# MEB-Quectel-BG96-v1_2_0.net
KiCad netlist of a schematic drawn in EAGLE
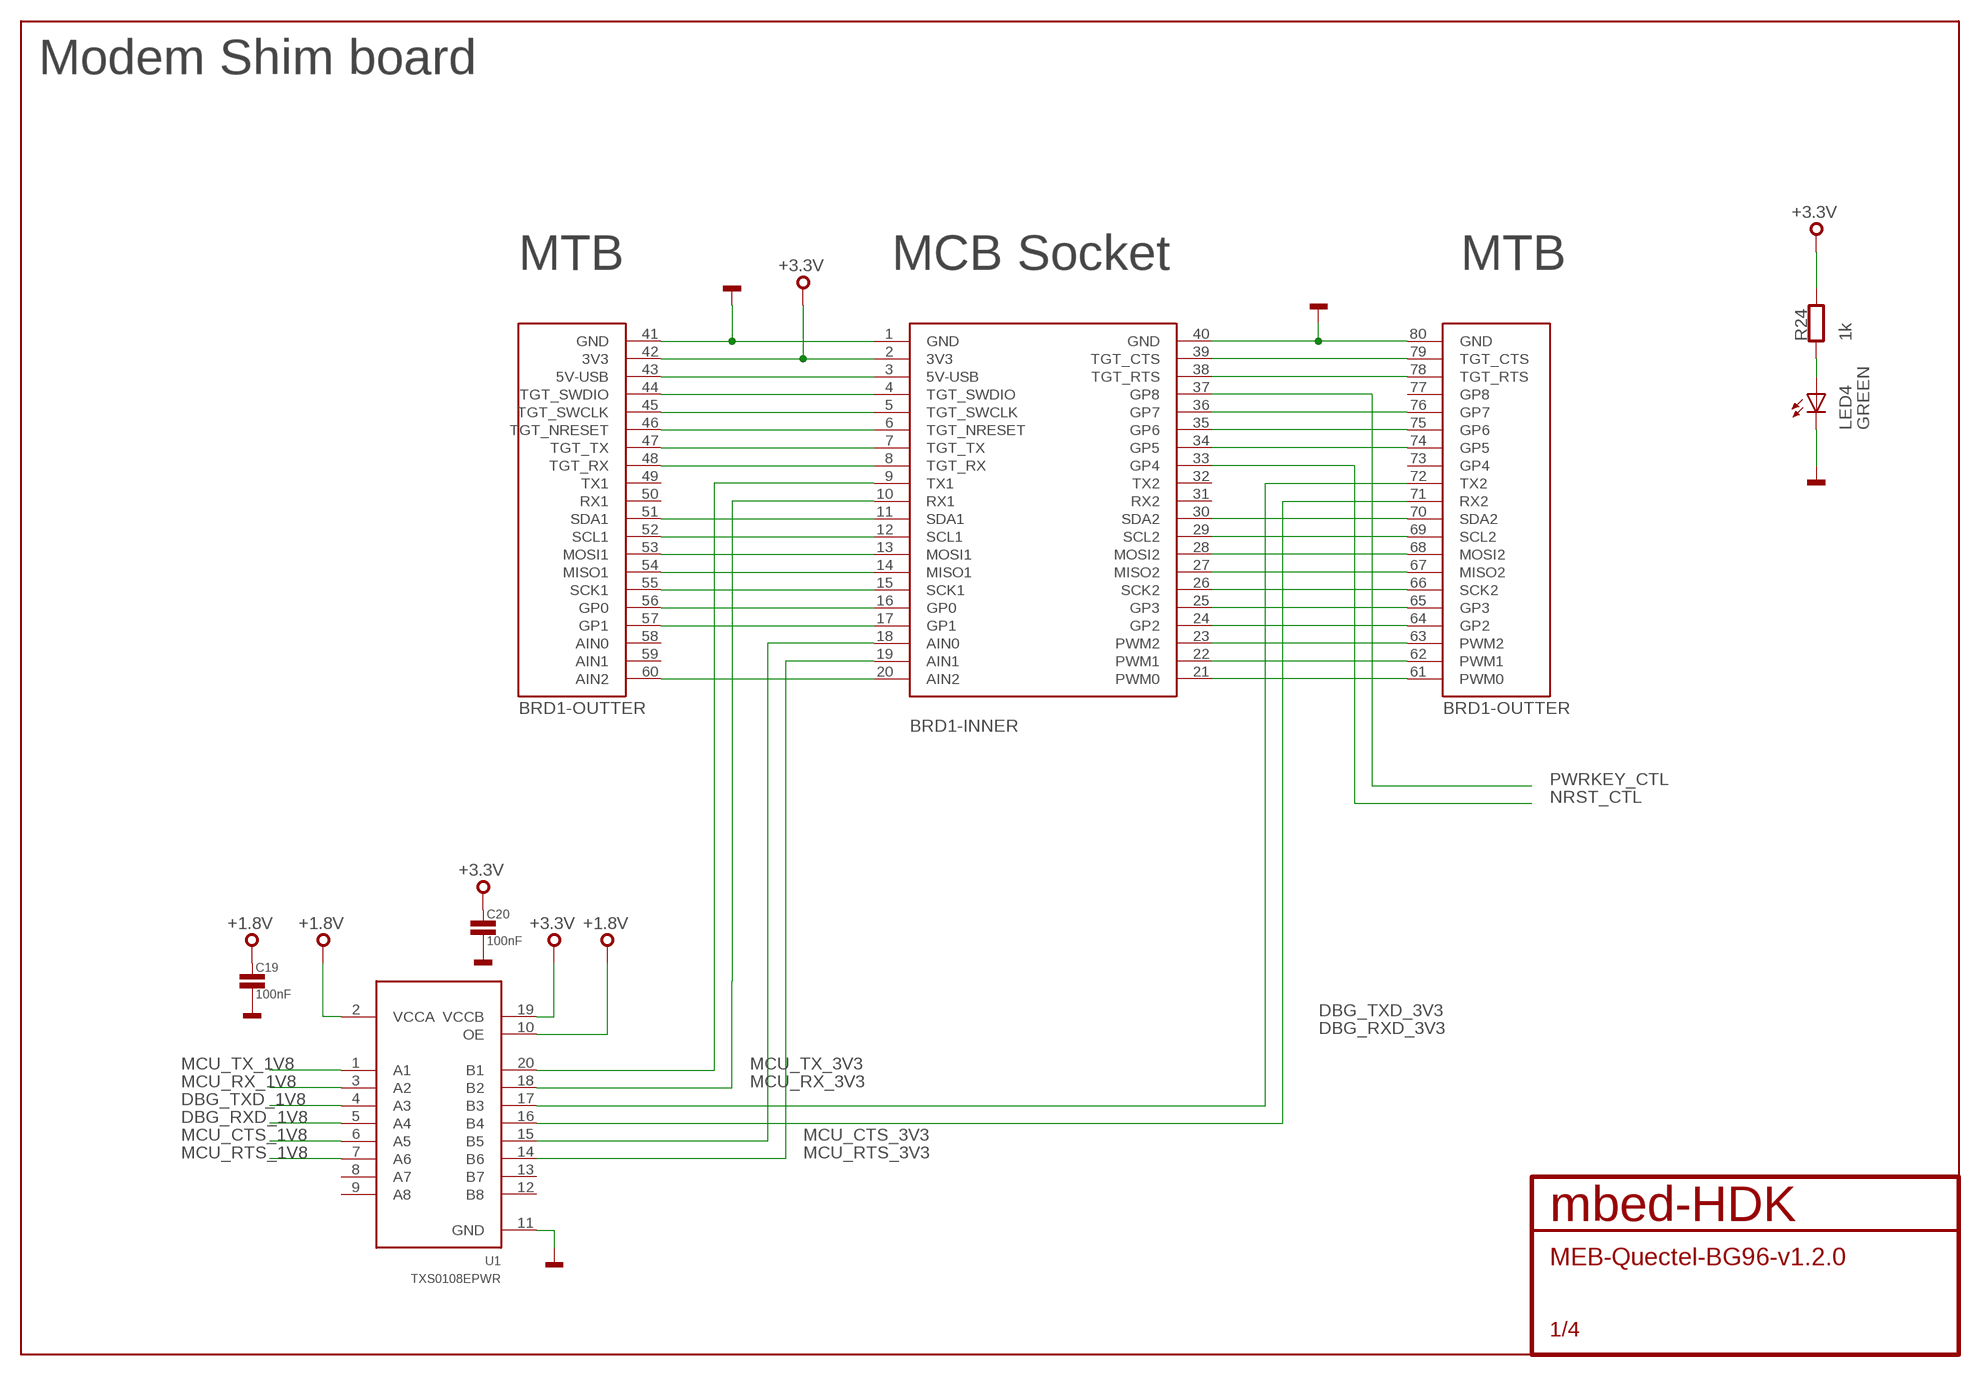
[diagram p0: schematic, sheet 1]
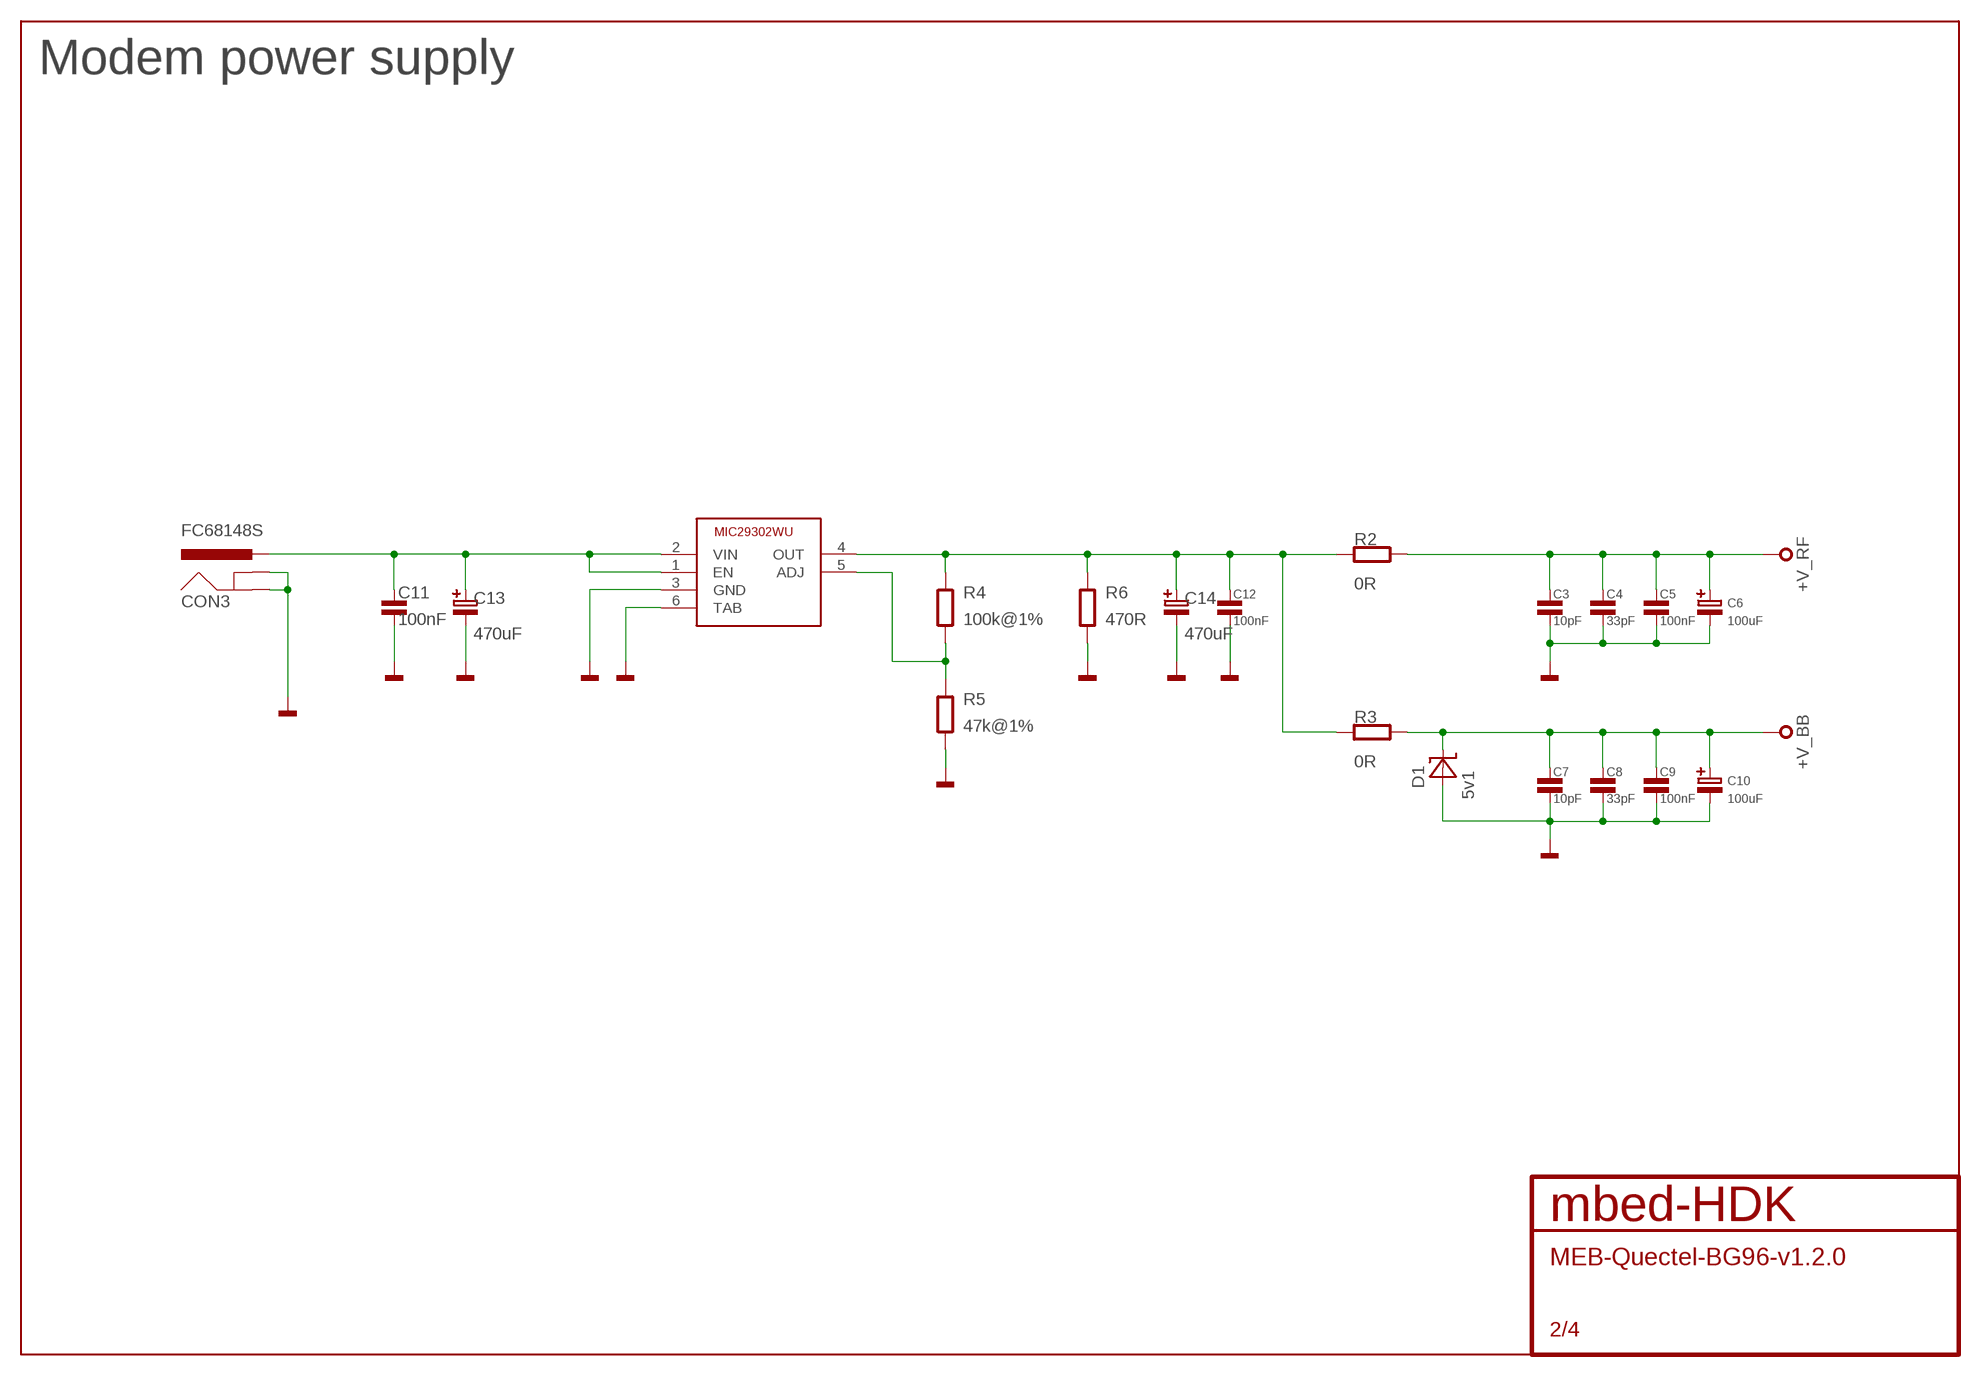
[diagram p1: schematic, sheet 2]
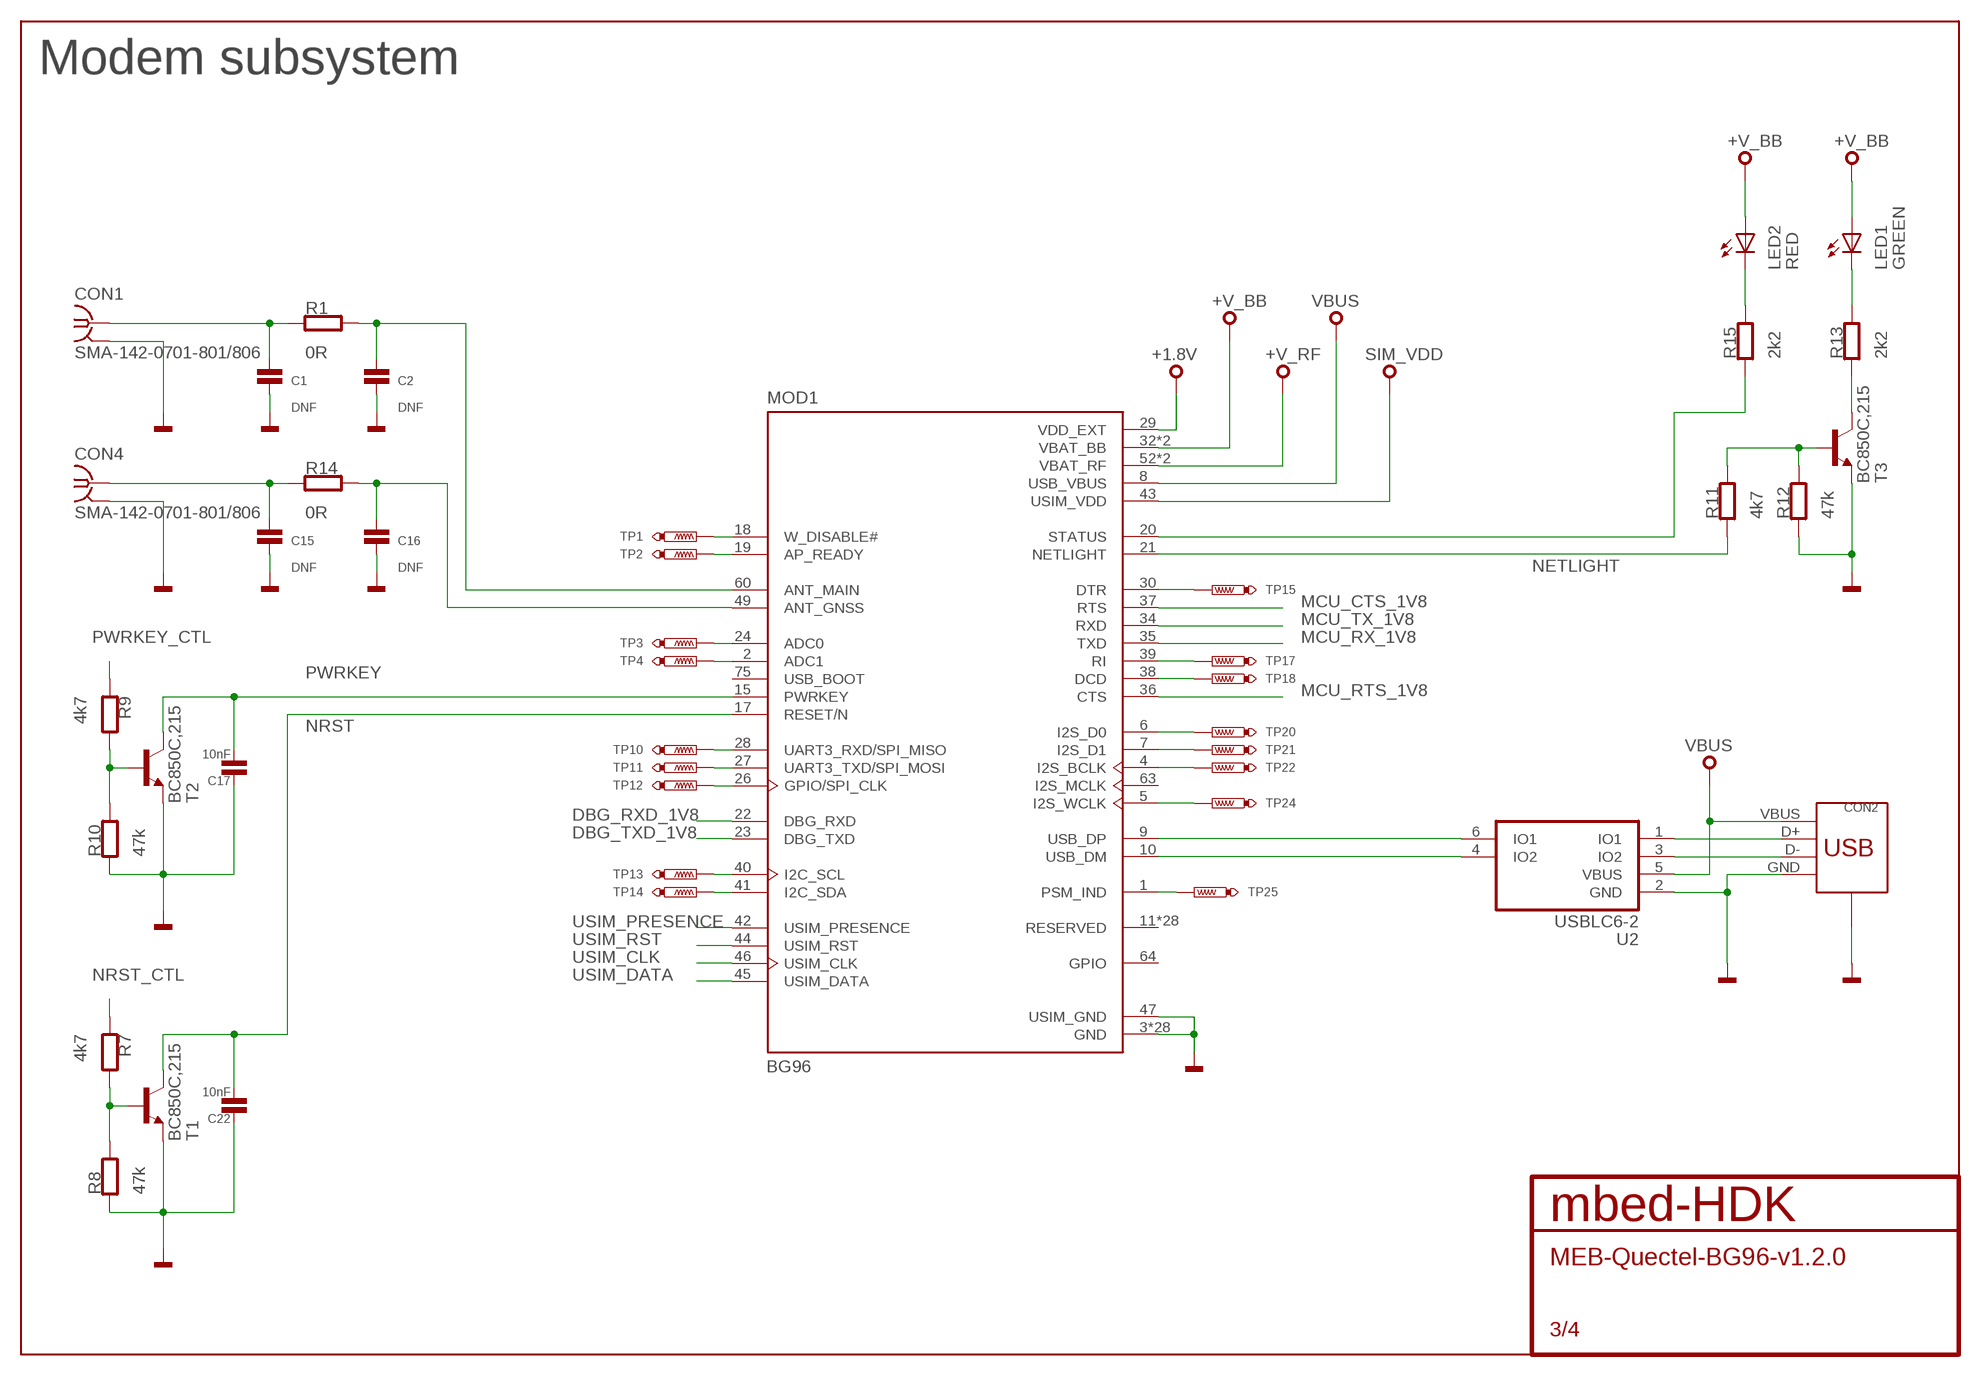
[diagram p2: schematic, sheet 3]
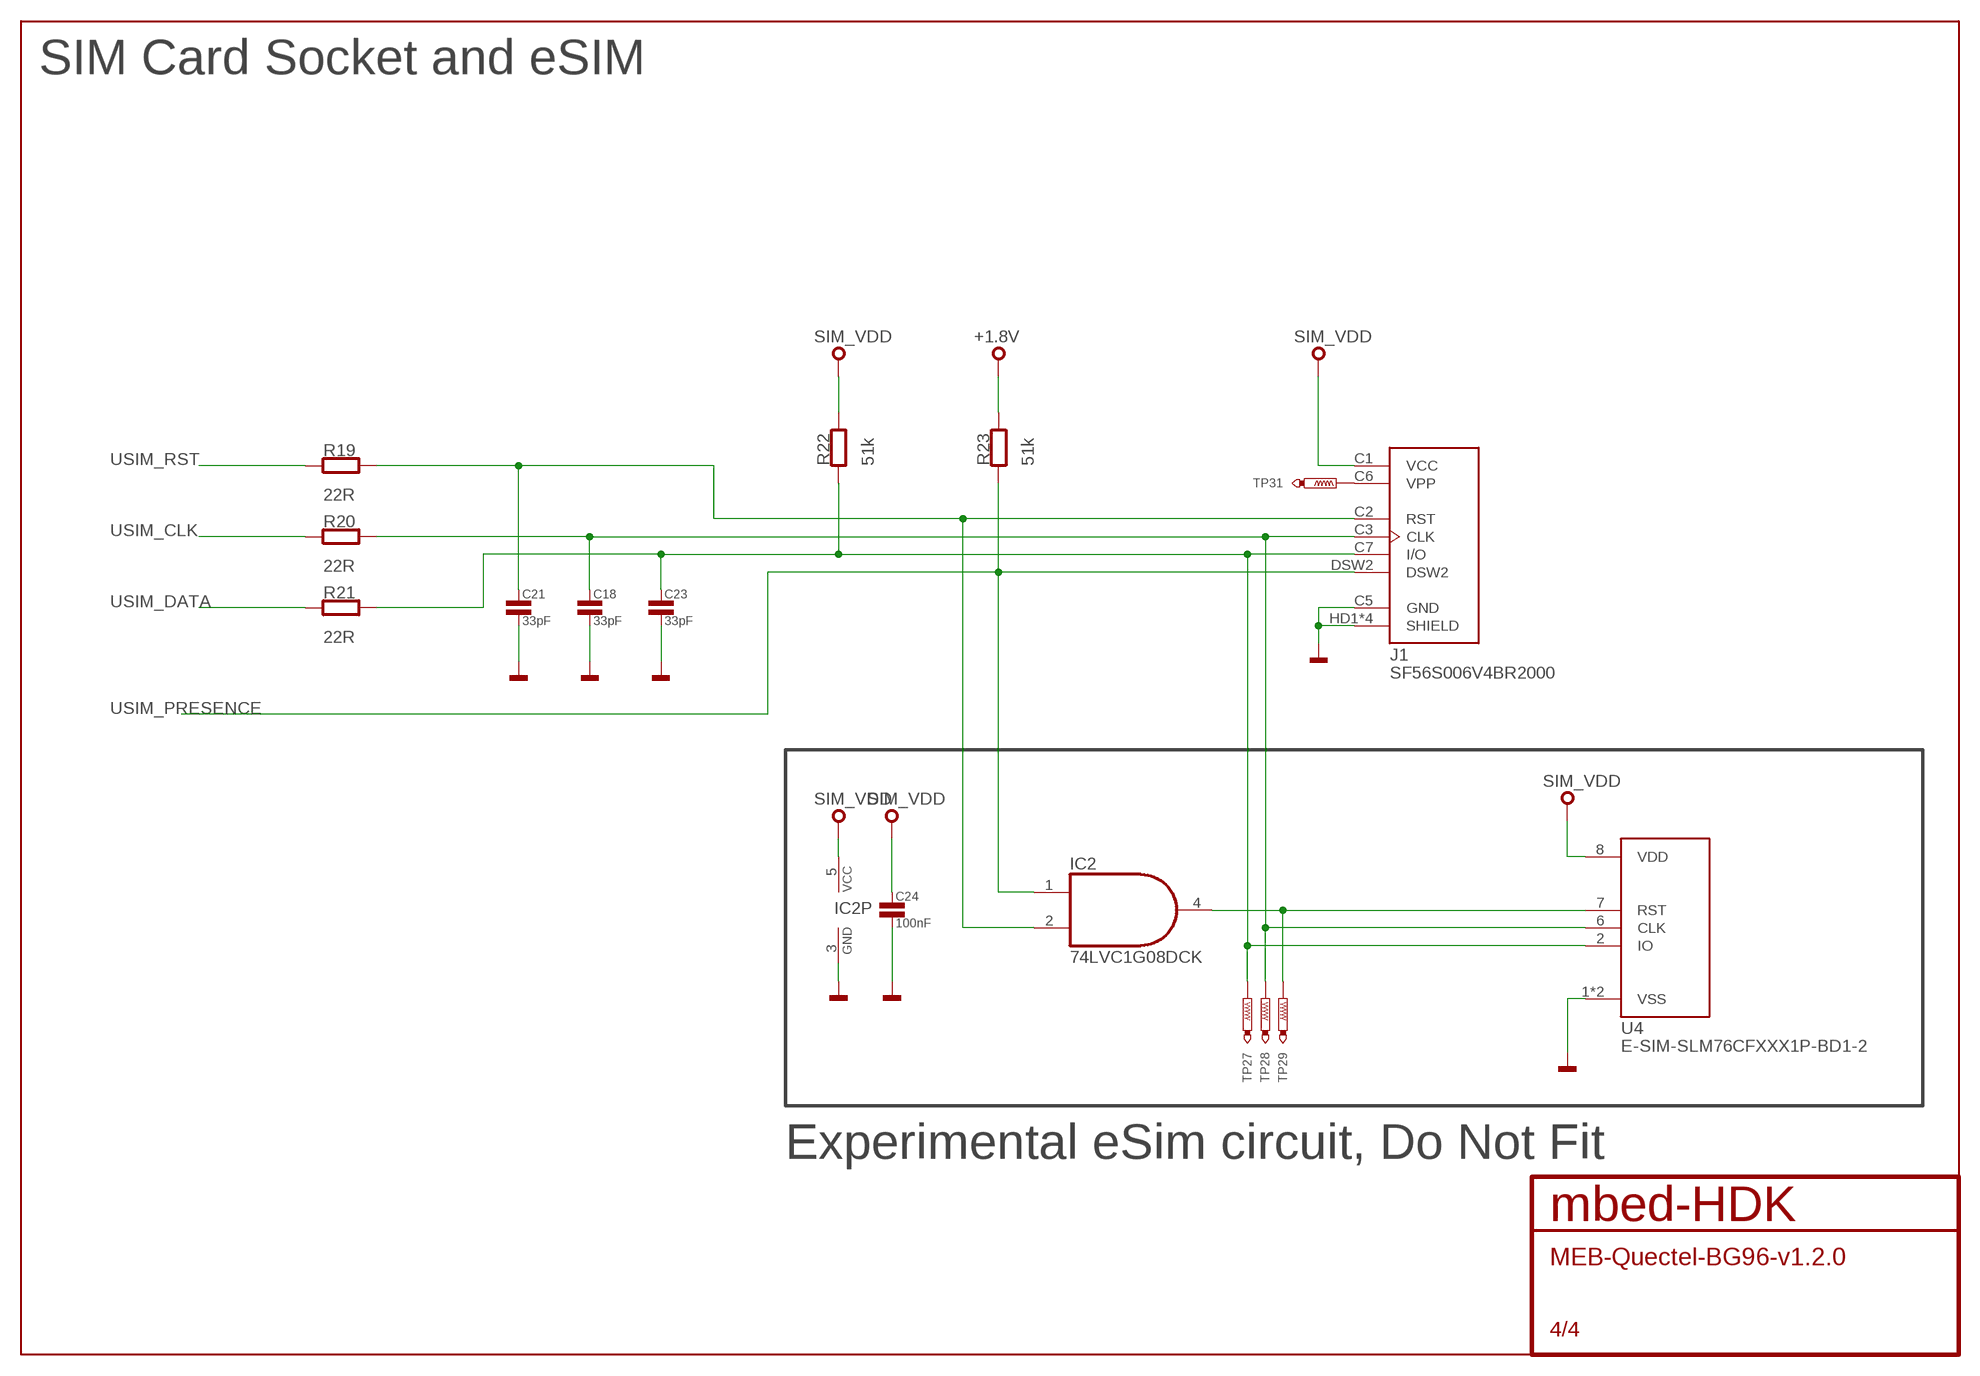
[diagram p3: schematic, sheet 4]

(export (version "E")
  (design (tool "Eeschema 10.0.6"))
  (components
    (comp (ref "C18")
      (value "33pF")
      (footprint "eagle-import:0603")
      (libsource (lib "eagle-import") (part "C0603"))
    )
    (comp (ref "C21")
      (value "33pF")
      (footprint "eagle-import:0603")
      (libsource (lib "eagle-import") (part "C0603"))
    )
    (comp (ref "C23")
      (value "33pF")
      (footprint "eagle-import:0603")
      (libsource (lib "eagle-import") (part "C0603"))
    )
    (comp (ref "C24")
      (value "100nF")
      (footprint "eagle-import:0603")
      (libsource (lib "eagle-import") (part "C0603"))
    )
    (comp (ref "IC2")
      (value "74LVC1G08DCK")
      (footprint "eagle-import:SC70-5")
      (libsource (lib "eagle-import") (part "741G08DCKLVC"))
    )
    (comp (ref "J1")
      (value "SF56S006V4BR2000")
      (footprint "eagle-import:JAE_SF56S006V4BR2000")
      (fields (field (name "DIGI-KEY_PART_NUMBER") "670-2834-1-ND") (field (name "MF") "JAE Electronics"))
      (libsource (lib "eagle-import") (part "SF56S006V4BR2000"))
    )
    (comp (ref "R19")
      (value "22R")
      (footprint "eagle-import:0603")
      (libsource (lib "eagle-import") (part "R0603"))
    )
    (comp (ref "R20")
      (value "22R")
      (footprint "eagle-import:0603")
      (libsource (lib "eagle-import") (part "R0603"))
    )
    (comp (ref "R21")
      (value "22R")
      (footprint "eagle-import:0603")
      (libsource (lib "eagle-import") (part "R0603"))
    )
    (comp (ref "R22")
      (value "51k")
      (footprint "eagle-import:0603")
      (libsource (lib "eagle-import") (part "R0603"))
    )
    (comp (ref "R23")
      (value "51k")
      (footprint "eagle-import:0603")
      (libsource (lib "eagle-import") (part "R0603"))
    )
    (comp (ref "TP27")
      (value "TEST_POINT-50R-SMD")
      (footprint "eagle-import:TP50-SMD")
      (libsource (lib "eagle-import") (part "TEST_POINT-50R-SMD"))
    )
    (comp (ref "TP28")
      (value "TEST_POINT-50R-SMD")
      (footprint "eagle-import:TP50-SMD")
      (libsource (lib "eagle-import") (part "TEST_POINT-50R-SMD"))
    )
    (comp (ref "TP29")
      (value "TEST_POINT-50R-SMD")
      (footprint "eagle-import:TP50-SMD")
      (libsource (lib "eagle-import") (part "TEST_POINT-50R-SMD"))
    )
    (comp (ref "TP31")
      (value "TEST_POINT-50R-SMD")
      (footprint "eagle-import:TP50-SMD")
      (libsource (lib "eagle-import") (part "TEST_POINT-50R-SMD"))
    )
    (comp (ref "U4")
      (value "E-SIM-SLM76CFXXX1P-BD1-2")
      (footprint "eagle-import:VQFN-8-1")
      (libsource (lib "eagle-import") (part "E-SIM-SLM76CFXXX1P-BD1-2"))
    )
    (comp (ref "BRD1")
      (value "MODULE-SHIM")
      (footprint "eagle-import:MODULE_SOCKET")
      (libsource (lib "eagle-import") (part "MODULE-SHIM"))
    )
    (comp (ref "C19")
      (value "100nF")
      (footprint "eagle-import:0603")
      (libsource (lib "eagle-import") (part "C0603"))
    )
    (comp (ref "C20")
      (value "100nF")
      (footprint "eagle-import:0603")
      (libsource (lib "eagle-import") (part "C0603"))
    )
    (comp (ref "LED4")
      (value "GREEN")
      (footprint "eagle-import:CHIPLED_0603")
      (libsource (lib "eagle-import") (part "LED0603"))
    )
    (comp (ref "R24")
      (value "1k")
      (footprint "eagle-import:0603")
      (libsource (lib "eagle-import") (part "R0603"))
    )
    (comp (ref "U1")
      (value "TXS0108EPWR")
      (footprint "eagle-import:TSSOP-20")
      (fields (field (name "MF") "Texas Instruments"))
      (libsource (lib "eagle-import") (part "TXS0108EPWR"))
    )
    (comp (ref "C3")
      (value "10pF")
      (footprint "eagle-import:0603")
      (libsource (lib "eagle-import") (part "C0603"))
    )
    (comp (ref "C4")
      (value "33pF")
      (footprint "eagle-import:0603")
      (libsource (lib "eagle-import") (part "C0603"))
    )
    (comp (ref "C5")
      (value "100nF")
      (footprint "eagle-import:0603")
      (libsource (lib "eagle-import") (part "C0603"))
    )
    (comp (ref "C6")
      (value "100uF")
      (footprint "eagle-import:SMC_A")
      (libsource (lib "eagle-import") (part "C-POLA"))
    )
    (comp (ref "C7")
      (value "10pF")
      (footprint "eagle-import:0603")
      (libsource (lib "eagle-import") (part "C0603"))
    )
    (comp (ref "C8")
      (value "33pF")
      (footprint "eagle-import:0603")
      (libsource (lib "eagle-import") (part "C0603"))
    )
    (comp (ref "C9")
      (value "100nF")
      (footprint "eagle-import:0603")
      (libsource (lib "eagle-import") (part "C0603"))
    )
    (comp (ref "C10")
      (value "100uF")
      (footprint "eagle-import:SMC_A")
      (libsource (lib "eagle-import") (part "C-POLA"))
    )
    (comp (ref "C11")
      (value "100nF")
      (footprint "eagle-import:0603")
      (libsource (lib "eagle-import") (part "C0603"))
    )
    (comp (ref "C12")
      (value "100nF")
      (footprint "eagle-import:0603")
      (libsource (lib "eagle-import") (part "C0603"))
    )
    (comp (ref "C13")
      (value "470uF")
      (footprint "eagle-import:PANASONIC_F")
      (libsource (lib "eagle-import") (part "C-POL_F"))
    )
    (comp (ref "C14")
      (value "470uF")
      (footprint "eagle-import:PANASONIC_F")
      (libsource (lib "eagle-import") (part "C-POL_F"))
    )
    (comp (ref "CON3")
      (value "FC68148S")
      (footprint "eagle-import:FC68148S")
      (fields (field (name "MF") "Cliff"))
      (libsource (lib "eagle-import") (part "FC68148S"))
    )
    (comp (ref "D1")
      (value "5v1")
      (footprint "eagle-import:SOD123")
      (libsource (lib "eagle-import") (part "DIODE-ZENER"))
    )
    (comp (ref "IC1")
      (value "MIC29302WU")
      (footprint "eagle-import:TO263-5")
      (fields (field (name "MF") "Microchip"))
      (libsource (lib "eagle-import") (part "MIC29302WU"))
    )
    (comp (ref "R2")
      (value "0R")
      (footprint "eagle-import:0603")
      (libsource (lib "eagle-import") (part "R0603"))
    )
    (comp (ref "R3")
      (value "0R")
      (footprint "eagle-import:0603")
      (libsource (lib "eagle-import") (part "R0603"))
    )
    (comp (ref "R4")
      (value "100k@1%")
      (footprint "eagle-import:0603")
      (libsource (lib "eagle-import") (part "R0603"))
    )
    (comp (ref "R5")
      (value "47k@1%")
      (footprint "eagle-import:0603")
      (libsource (lib "eagle-import") (part "R0603"))
    )
    (comp (ref "R6")
      (value "470R")
      (footprint "eagle-import:0603")
      (libsource (lib "eagle-import") (part "R0603"))
    )
    (comp (ref "C1")
      (value "DNF")
      (footprint "eagle-import:0603")
      (libsource (lib "eagle-import") (part "C0603"))
    )
    (comp (ref "C2")
      (value "DNF")
      (footprint "eagle-import:0603")
      (libsource (lib "eagle-import") (part "C0603"))
    )
    (comp (ref "C15")
      (value "DNF")
      (footprint "eagle-import:0603")
      (libsource (lib "eagle-import") (part "C0603"))
    )
    (comp (ref "C16")
      (value "DNF")
      (footprint "eagle-import:0603")
      (libsource (lib "eagle-import") (part "C0603"))
    )
    (comp (ref "C17")
      (value "10nF")
      (footprint "eagle-import:0603")
      (libsource (lib "eagle-import") (part "C0603"))
    )
    (comp (ref "C22")
      (value "10nF")
      (footprint "eagle-import:0603")
      (libsource (lib "eagle-import") (part "C0603"))
    )
    (comp (ref "CON1")
      (value "SMA-142-0701-801/806")
      (footprint "eagle-import:J502-ND-142-0701-801_806")
      (fields (field (name "MF") "JOHNSON COMPONENTS") (field (name "MPN") "142-0701-801"))
      (libsource (lib "eagle-import") (part "SMA-142-0701-801/806"))
    )
    (comp (ref "CON2")
      (value "47346-0001")
      (footprint "eagle-import:USB-MICRO-B-H")
      (fields (field (name "MF") "MOLEX"))
      (libsource (lib "eagle-import") (part "47346-0001"))
    )
    (comp (ref "CON4")
      (value "SMA-142-0701-801/806")
      (footprint "eagle-import:J502-ND-142-0701-801_806")
      (fields (field (name "MF") "JOHNSON COMPONENTS") (field (name "MPN") "142-0701-801"))
      (libsource (lib "eagle-import") (part "SMA-142-0701-801/806"))
    )
    (comp (ref "LED1")
      (value "GREEN")
      (footprint "eagle-import:CHIPLED_0603")
      (libsource (lib "eagle-import") (part "LED0603"))
    )
    (comp (ref "LED2")
      (value "RED")
      (footprint "eagle-import:CHIPLED_0603")
      (libsource (lib "eagle-import") (part "LED0603"))
    )
    (comp (ref "MOD1")
      (value "BG96")
      (footprint "eagle-import:LTE_MODULE_BG96")
      (fields (field (name "MF") "Quectel"))
      (libsource (lib "eagle-import") (part "BG96"))
    )
    (comp (ref "R1")
      (value "0R")
      (footprint "eagle-import:0603")
      (libsource (lib "eagle-import") (part "R0603"))
    )
    (comp (ref "R7")
      (value "4k7")
      (footprint "eagle-import:0603")
      (libsource (lib "eagle-import") (part "R0603"))
    )
    (comp (ref "R8")
      (value "47k")
      (footprint "eagle-import:0603")
      (libsource (lib "eagle-import") (part "R0603"))
    )
    (comp (ref "R9")
      (value "4k7")
      (footprint "eagle-import:0603")
      (libsource (lib "eagle-import") (part "R0603"))
    )
    (comp (ref "R10")
      (value "47k")
      (footprint "eagle-import:0603")
      (libsource (lib "eagle-import") (part "R0603"))
    )
    (comp (ref "R11")
      (value "4k7")
      (footprint "eagle-import:0603")
      (libsource (lib "eagle-import") (part "R0603"))
    )
    (comp (ref "R12")
      (value "47k")
      (footprint "eagle-import:0603")
      (libsource (lib "eagle-import") (part "R0603"))
    )
    (comp (ref "R13")
      (value "2k2")
      (footprint "eagle-import:0603")
      (libsource (lib "eagle-import") (part "R0603"))
    )
    (comp (ref "R14")
      (value "0R")
      (footprint "eagle-import:0603")
      (libsource (lib "eagle-import") (part "R0603"))
    )
    (comp (ref "R15")
      (value "2k2")
      (footprint "eagle-import:0603")
      (libsource (lib "eagle-import") (part "R0603"))
    )
    (comp (ref "T1")
      (value "BC850C,215")
      (footprint "eagle-import:SOT23-3")
      (fields (field (name "MF") "NXP Semiconductors"))
      (libsource (lib "eagle-import") (part "BC850C,215"))
    )
    (comp (ref "T2")
      (value "BC850C,215")
      (footprint "eagle-import:SOT23-3")
      (fields (field (name "MF") "NXP Semiconductors"))
      (libsource (lib "eagle-import") (part "BC850C,215"))
    )
    (comp (ref "T3")
      (value "BC850C,215")
      (footprint "eagle-import:SOT23-3")
      (fields (field (name "MF") "NXP Semiconductors"))
      (libsource (lib "eagle-import") (part "BC850C,215"))
    )
    (comp (ref "TP1")
      (value "TEST_POINT-50R-SMD")
      (footprint "eagle-import:TP50-SMD")
      (libsource (lib "eagle-import") (part "TEST_POINT-50R-SMD"))
    )
    (comp (ref "TP2")
      (value "TEST_POINT-50R-SMD")
      (footprint "eagle-import:TP50-SMD")
      (libsource (lib "eagle-import") (part "TEST_POINT-50R-SMD"))
    )
    (comp (ref "TP3")
      (value "TEST_POINT-50R-SMD")
      (footprint "eagle-import:TP50-SMD")
      (libsource (lib "eagle-import") (part "TEST_POINT-50R-SMD"))
    )
    (comp (ref "TP4")
      (value "TEST_POINT-50R-SMD")
      (footprint "eagle-import:TP50-SMD")
      (libsource (lib "eagle-import") (part "TEST_POINT-50R-SMD"))
    )
    (comp (ref "TP10")
      (value "TEST_POINT-50R-SMD")
      (footprint "eagle-import:TP50-SMD")
      (libsource (lib "eagle-import") (part "TEST_POINT-50R-SMD"))
    )
    (comp (ref "TP11")
      (value "TEST_POINT-50R-SMD")
      (footprint "eagle-import:TP50-SMD")
      (libsource (lib "eagle-import") (part "TEST_POINT-50R-SMD"))
    )
    (comp (ref "TP12")
      (value "TEST_POINT-50R-SMD")
      (footprint "eagle-import:TP50-SMD")
      (libsource (lib "eagle-import") (part "TEST_POINT-50R-SMD"))
    )
    (comp (ref "TP13")
      (value "TEST_POINT-50R-SMD")
      (footprint "eagle-import:TP50-SMD")
      (libsource (lib "eagle-import") (part "TEST_POINT-50R-SMD"))
    )
    (comp (ref "TP14")
      (value "TEST_POINT-50R-SMD")
      (footprint "eagle-import:TP50-SMD")
      (libsource (lib "eagle-import") (part "TEST_POINT-50R-SMD"))
    )
    (comp (ref "TP15")
      (value "TEST_POINT-50R-SMD")
      (footprint "eagle-import:TP50-SMD")
      (libsource (lib "eagle-import") (part "TEST_POINT-50R-SMD"))
    )
    (comp (ref "TP17")
      (value "TEST_POINT-50R-SMD")
      (footprint "eagle-import:TP50-SMD")
      (libsource (lib "eagle-import") (part "TEST_POINT-50R-SMD"))
    )
    (comp (ref "TP18")
      (value "TEST_POINT-50R-SMD")
      (footprint "eagle-import:TP50-SMD")
      (libsource (lib "eagle-import") (part "TEST_POINT-50R-SMD"))
    )
    (comp (ref "TP20")
      (value "TEST_POINT-50R-SMD")
      (footprint "eagle-import:TP50-SMD")
      (libsource (lib "eagle-import") (part "TEST_POINT-50R-SMD"))
    )
    (comp (ref "TP21")
      (value "TEST_POINT-50R-SMD")
      (footprint "eagle-import:TP50-SMD")
      (libsource (lib "eagle-import") (part "TEST_POINT-50R-SMD"))
    )
    (comp (ref "TP22")
      (value "TEST_POINT-50R-SMD")
      (footprint "eagle-import:TP50-SMD")
      (libsource (lib "eagle-import") (part "TEST_POINT-50R-SMD"))
    )
    (comp (ref "TP24")
      (value "TEST_POINT-50R-SMD")
      (footprint "eagle-import:TP50-SMD")
      (libsource (lib "eagle-import") (part "TEST_POINT-50R-SMD"))
    )
    (comp (ref "TP25")
      (value "TEST_POINT-50R-SMD")
      (footprint "eagle-import:TP50-SMD")
      (libsource (lib "eagle-import") (part "TEST_POINT-50R-SMD"))
    )
    (comp (ref "U2")
      (value "USBLC6-2SC6")
      (footprint "eagle-import:SOT23-6L")
      (fields (field (name "MF") "STMicro"))
      (libsource (lib "eagle-import") (part "USBLC6-2SC6"))
    )
  )
  (nets
    (net (code "1") (name "+1.8V") (class "Default")
      (node (ref "C19") (pin "1") (pinfunction "P$1_1") (pintype "passive"))
      (node (ref "MOD1") (pin "29") (pinfunction "VDD_EXT_29") (pintype "power_in"))
      (node (ref "R23") (pin "2") (pinfunction "P$2_2") (pintype "passive"))
      (node (ref "U1") (pin "10") (pinfunction "OE_10") (pintype "bidirectional"))
      (node (ref "U1") (pin "2") (pinfunction "VCCA_2") (pintype "bidirectional"))
    )
    (net (code "2") (name "+3.3V") (class "Default")
      (node (ref "BRD1") (pin "2") (pinfunction "3V3_2") (pintype "bidirectional"))
      (node (ref "BRD1") (pin "42") (pinfunction "3V3_42") (pintype "bidirectional"))
      (node (ref "C20") (pin "1") (pinfunction "P$1_1") (pintype "passive"))
      (node (ref "R24") (pin "2") (pinfunction "P$2_2") (pintype "passive"))
      (node (ref "U1") (pin "19") (pinfunction "VCCB_19") (pintype "bidirectional"))
    )
    (net (code "3") (name "+V_BB") (class "Default")
      (node (ref "C10") (pin "+") (pinfunction "+_+") (pintype "passive"))
      (node (ref "C7") (pin "1") (pinfunction "P$1_1") (pintype "passive"))
      (node (ref "C8") (pin "1") (pinfunction "P$1_1") (pintype "passive"))
      (node (ref "C9") (pin "1") (pinfunction "P$1_1") (pintype "passive"))
      (node (ref "D1") (pin "2") (pinfunction "C_2") (pintype "passive"))
      (node (ref "LED1") (pin "A") (pinfunction "A_A") (pintype "passive"))
      (node (ref "LED2") (pin "A") (pinfunction "A_A") (pintype "passive"))
      (node (ref "MOD1") (pin "32") (pinfunction "VBAT_BB_32") (pintype "power_in"))
      (node (ref "MOD1") (pin "33") (pinfunction "VBAT_BB_33") (pintype "power_in"))
      (node (ref "R3") (pin "2") (pinfunction "P$2_2") (pintype "passive"))
    )
    (net (code "4") (name "+V_RF") (class "Default")
      (node (ref "C3") (pin "1") (pinfunction "P$1_1") (pintype "passive"))
      (node (ref "C4") (pin "1") (pinfunction "P$1_1") (pintype "passive"))
      (node (ref "C5") (pin "1") (pinfunction "P$1_1") (pintype "passive"))
      (node (ref "C6") (pin "+") (pinfunction "+_+") (pintype "passive"))
      (node (ref "MOD1") (pin "52") (pinfunction "VBAT_RF_52") (pintype "power_in"))
      (node (ref "MOD1") (pin "53") (pinfunction "VBAT_RF_53") (pintype "power_in"))
      (node (ref "R2") (pin "2") (pinfunction "P$2_2") (pintype "passive"))
    )
    (net (code "5") (name "DBG_RXD_1V8") (class "Default")
      (node (ref "MOD1") (pin "22") (pinfunction "DBG_RXD_22") (pintype "input"))
      (node (ref "U1") (pin "5") (pinfunction "A4_5") (pintype "bidirectional"))
    )
    (net (code "6") (name "DBG_RXD_3V3") (class "Default")
      (node (ref "BRD1") (pin "71") (pinfunction "RX2_71") (pintype "bidirectional"))
      (node (ref "U1") (pin "16") (pinfunction "B4_16") (pintype "bidirectional"))
    )
    (net (code "7") (name "DBG_TXD_1V8") (class "Default")
      (node (ref "MOD1") (pin "23") (pinfunction "DBG_TXD_23") (pintype "output"))
      (node (ref "U1") (pin "4") (pinfunction "A3_4") (pintype "bidirectional"))
    )
    (net (code "8") (name "DBG_TXD_3V3") (class "Default")
      (node (ref "BRD1") (pin "72") (pinfunction "TX2_72") (pintype "bidirectional"))
      (node (ref "U1") (pin "17") (pinfunction "B3_17") (pintype "bidirectional"))
    )
    (net (code "9") (name "GND") (class "Default")
      (node (ref "BRD1") (pin "1") (pinfunction "GND_1") (pintype "bidirectional"))
      (node (ref "BRD1") (pin "40") (pinfunction "GND_40") (pintype "bidirectional"))
      (node (ref "BRD1") (pin "41") (pinfunction "GND_41") (pintype "bidirectional"))
      (node (ref "BRD1") (pin "80") (pinfunction "GND_80") (pintype "bidirectional"))
      (node (ref "C1") (pin "1") (pinfunction "P$1_1") (pintype "passive"))
      (node (ref "C10") (pin "-") (pinfunction "-_-") (pintype "passive"))
      (node (ref "C11") (pin "2") (pinfunction "P$2_2") (pintype "passive"))
      (node (ref "C12") (pin "2") (pinfunction "P$2_2") (pintype "passive"))
      (node (ref "C13") (pin "-") (pinfunction "-_-") (pintype "passive"))
      (node (ref "C14") (pin "-") (pinfunction "-_-") (pintype "passive"))
      (node (ref "C15") (pin "1") (pinfunction "P$1_1") (pintype "passive"))
      (node (ref "C16") (pin "1") (pinfunction "P$1_1") (pintype "passive"))
      (node (ref "C17") (pin "1") (pinfunction "P$1_1") (pintype "passive"))
      (node (ref "C18") (pin "2") (pinfunction "P$2_2") (pintype "passive"))
      (node (ref "C19") (pin "2") (pinfunction "P$2_2") (pintype "passive"))
      (node (ref "C2") (pin "1") (pinfunction "P$1_1") (pintype "passive"))
      (node (ref "C20") (pin "2") (pinfunction "P$2_2") (pintype "passive"))
      (node (ref "C21") (pin "2") (pinfunction "P$2_2") (pintype "passive"))
      (node (ref "C22") (pin "1") (pinfunction "P$1_1") (pintype "passive"))
      (node (ref "C23") (pin "2") (pinfunction "P$2_2") (pintype "passive"))
      (node (ref "C24") (pin "2") (pinfunction "P$2_2") (pintype "passive"))
      (node (ref "C3") (pin "2") (pinfunction "P$2_2") (pintype "passive"))
      (node (ref "C4") (pin "2") (pinfunction "P$2_2") (pintype "passive"))
      (node (ref "C5") (pin "2") (pinfunction "P$2_2") (pintype "passive"))
      (node (ref "C6") (pin "-") (pinfunction "-_-") (pintype "passive"))
      (node (ref "C7") (pin "2") (pinfunction "P$2_2") (pintype "passive"))
      (node (ref "C8") (pin "2") (pinfunction "P$2_2") (pintype "passive"))
      (node (ref "C9") (pin "2") (pinfunction "P$2_2") (pintype "passive"))
      (node (ref "CON1") (pin "G@1") (pinfunction "2_G@1") (pintype "passive"))
      (node (ref "CON1") (pin "G@2") (pinfunction "2_G@2") (pintype "passive"))
      (node (ref "CON1") (pin "G@3") (pinfunction "2_G@3") (pintype "passive"))
      (node (ref "CON1") (pin "G@4") (pinfunction "2_G@4") (pintype "passive"))
      (node (ref "CON2") (pin "GND") (pinfunction "GND_GND") (pintype "bidirectional"))
      (node (ref "CON2") (pin "GND1") (pinfunction "SHEILD_GND1") (pintype "bidirectional"))
      (node (ref "CON2") (pin "GND2") (pinfunction "SHEILD_GND2") (pintype "bidirectional"))
      (node (ref "CON2") (pin "GND3") (pinfunction "SHEILD_GND3") (pintype "bidirectional"))
      (node (ref "CON2") (pin "GND4") (pinfunction "SHEILD_GND4") (pintype "bidirectional"))
      (node (ref "CON3") (pin "2") (pinfunction "GNDBREAK_2") (pintype "bidirectional"))
      (node (ref "CON3") (pin "3") (pinfunction "GND_3") (pintype "bidirectional"))
      (node (ref "CON4") (pin "G@1") (pinfunction "2_G@1") (pintype "passive"))
      (node (ref "CON4") (pin "G@2") (pinfunction "2_G@2") (pintype "passive"))
      (node (ref "CON4") (pin "G@3") (pinfunction "2_G@3") (pintype "passive"))
      (node (ref "CON4") (pin "G@4") (pinfunction "2_G@4") (pintype "passive"))
      (node (ref "D1") (pin "1") (pinfunction "A_1") (pintype "passive"))
      (node (ref "IC1") (pin "3") (pinfunction "GND_3") (pintype "bidirectional"))
      (node (ref "IC1") (pin "6") (pinfunction "TAB_6") (pintype "bidirectional"))
      (node (ref "IC2") (pin "3") (pinfunction "GND_3") (pintype "power_in"))
      (node (ref "J1") (pin "C5") (pinfunction "GND_C5") (pintype "power_in"))
      (node (ref "J1") (pin "HD1") (pinfunction "SHIELD_HD1") (pintype "power_in"))
      (node (ref "J1") (pin "HD2,DSW1") (pinfunction "SHIELD_HD2,DSW1") (pintype "power_in"))
      (node (ref "J1") (pin "HD3") (pinfunction "SHIELD_HD3") (pintype "power_in"))
      (node (ref "J1") (pin "HD4") (pinfunction "SHIELD_HD4") (pintype "power_in"))
      (node (ref "LED4") (pin "C") (pinfunction "C_C") (pintype "passive"))
      (node (ref "MOD1") (pin "100") (pinfunction "GND_100") (pintype "power_in"))
      (node (ref "MOD1") (pin "101") (pinfunction "GND_101") (pintype "power_in"))
      (node (ref "MOD1") (pin "102") (pinfunction "GND_102") (pintype "power_in"))
      (node (ref "MOD1") (pin "3") (pinfunction "GND_3") (pintype "power_in"))
      (node (ref "MOD1") (pin "31") (pinfunction "GND_31") (pintype "power_in"))
      (node (ref "MOD1") (pin "47") (pinfunction "USIM_GND_47") (pintype "power_in"))
      (node (ref "MOD1") (pin "48") (pinfunction "GND_48") (pintype "power_in"))
      (node (ref "MOD1") (pin "50") (pinfunction "GND_50") (pintype "power_in"))
      (node (ref "MOD1") (pin "54") (pinfunction "GND_54") (pintype "power_in"))
      (node (ref "MOD1") (pin "55") (pinfunction "GND_55") (pintype "power_in"))
      (node (ref "MOD1") (pin "58") (pinfunction "GND_58") (pintype "power_in"))
      (node (ref "MOD1") (pin "59") (pinfunction "GND_59") (pintype "power_in"))
      (node (ref "MOD1") (pin "61") (pinfunction "GND_61") (pintype "power_in"))
      (node (ref "MOD1") (pin "62") (pinfunction "GND_62") (pintype "power_in"))
      (node (ref "MOD1") (pin "67") (pinfunction "GND_67") (pintype "power_in"))
      (node (ref "MOD1") (pin "68") (pinfunction "GND_68") (pintype "power_in"))
      (node (ref "MOD1") (pin "69") (pinfunction "GND_69") (pintype "power_in"))
      (node (ref "MOD1") (pin "70") (pinfunction "GND_70") (pintype "power_in"))
      (node (ref "MOD1") (pin "71") (pinfunction "GND_71") (pintype "power_in"))
      (node (ref "MOD1") (pin "72") (pinfunction "GND_72") (pintype "power_in"))
      (node (ref "MOD1") (pin "73") (pinfunction "GND_73") (pintype "power_in"))
      (node (ref "MOD1") (pin "74") (pinfunction "GND_74") (pintype "power_in"))
      (node (ref "MOD1") (pin "79") (pinfunction "GND_79") (pintype "power_in"))
      (node (ref "MOD1") (pin "80") (pinfunction "GND_80") (pintype "power_in"))
      (node (ref "MOD1") (pin "81") (pinfunction "GND_81") (pintype "power_in"))
      (node (ref "MOD1") (pin "82") (pinfunction "GND_82") (pintype "power_in"))
      (node (ref "MOD1") (pin "89") (pinfunction "GND_89") (pintype "power_in"))
      (node (ref "MOD1") (pin "90") (pinfunction "GND_90") (pintype "power_in"))
      (node (ref "MOD1") (pin "91") (pinfunction "GND_91") (pintype "power_in"))
      (node (ref "R10") (pin "1") (pinfunction "P$1_1") (pintype "passive"))
      (node (ref "R12") (pin "1") (pinfunction "P$1_1") (pintype "passive"))
      (node (ref "R5") (pin "1") (pinfunction "P$1_1") (pintype "passive"))
      (node (ref "R6") (pin "1") (pinfunction "P$1_1") (pintype "passive"))
      (node (ref "R8") (pin "1") (pinfunction "P$1_1") (pintype "passive"))
      (node (ref "T1") (pin "2") (pinfunction "E_2") (pintype "passive"))
      (node (ref "T2") (pin "2") (pinfunction "E_2") (pintype "passive"))
      (node (ref "T3") (pin "2") (pinfunction "E_2") (pintype "passive"))
      (node (ref "U1") (pin "11") (pinfunction "GND_11") (pintype "bidirectional"))
      (node (ref "U2") (pin "2") (pinfunction "GND_2") (pintype "bidirectional"))
      (node (ref "U4") (pin "1") (pinfunction "VSS_1") (pintype "bidirectional"))
      (node (ref "U4") (pin "P") (pinfunction "VSS_P") (pintype "bidirectional"))
    )
    (net (code "10") (name "MCU_CTS_1V8") (class "Default")
      (node (ref "MOD1") (pin "37") (pinfunction "RTS_37") (pintype "input"))
      (node (ref "U1") (pin "6") (pinfunction "A5_6") (pintype "bidirectional"))
    )
    (net (code "11") (name "MCU_CTS_3V3") (class "Default")
      (node (ref "BRD1") (pin "18") (pinfunction "AIN0_18") (pintype "bidirectional"))
      (node (ref "U1") (pin "15") (pinfunction "B5_15") (pintype "bidirectional"))
    )
    (net (code "12") (name "MCU_RTS_1V8") (class "Default")
      (node (ref "MOD1") (pin "36") (pinfunction "CTS_36") (pintype "output"))
      (node (ref "U1") (pin "7") (pinfunction "A6_7") (pintype "bidirectional"))
    )
    (net (code "13") (name "MCU_RTS_3V3") (class "Default")
      (node (ref "BRD1") (pin "19") (pinfunction "AIN1_19") (pintype "bidirectional"))
      (node (ref "U1") (pin "14") (pinfunction "B6_14") (pintype "bidirectional"))
    )
    (net (code "14") (name "MCU_RX_1V8") (class "Default")
      (node (ref "MOD1") (pin "35") (pinfunction "TXD_35") (pintype "output"))
      (node (ref "U1") (pin "3") (pinfunction "A2_3") (pintype "bidirectional"))
    )
    (net (code "15") (name "MCU_RX_3V3") (class "Default")
      (node (ref "BRD1") (pin "10") (pinfunction "RX1_10") (pintype "bidirectional"))
      (node (ref "U1") (pin "18") (pinfunction "B2_18") (pintype "bidirectional"))
    )
    (net (code "16") (name "MCU_TX_1V8") (class "Default")
      (node (ref "MOD1") (pin "34") (pinfunction "RXD_34") (pintype "input"))
      (node (ref "U1") (pin "1") (pinfunction "A1_1") (pintype "bidirectional"))
    )
    (net (code "17") (name "MCU_TX_3V3") (class "Default")
      (node (ref "BRD1") (pin "9") (pinfunction "TX1_9") (pintype "bidirectional"))
      (node (ref "U1") (pin "20") (pinfunction "B1_20") (pintype "bidirectional"))
    )
    (net (code "18") (name "NETLIGHT") (class "Default")
      (node (ref "MOD1") (pin "21") (pinfunction "NETLIGHT_21") (pintype "output"))
      (node (ref "R11") (pin "1") (pinfunction "P$1_1") (pintype "passive"))
    )
    (net (code "19") (name "NRST") (class "Default")
      (node (ref "C22") (pin "2") (pinfunction "P$2_2") (pintype "passive"))
      (node (ref "MOD1") (pin "17") (pinfunction "RESET/N_17") (pintype "input"))
      (node (ref "T1") (pin "3") (pinfunction "C_3") (pintype "passive"))
    )
    (net (code "20") (name "NRST_CTL") (class "Default")
      (node (ref "BRD1") (pin "33") (pinfunction "GP4_33") (pintype "bidirectional"))
      (node (ref "R7") (pin "1") (pinfunction "P$1_1") (pintype "passive"))
    )
    (net (code "21") (name "Net-(BRD1A-5V-USB)") (class "Default")
      (node (ref "BRD1") (pin "3") (pinfunction "5V-USB_3") (pintype "bidirectional"))
      (node (ref "BRD1") (pin "43") (pinfunction "5V-USB_43") (pintype "bidirectional"))
    )
    (net (code "22") (name "Net-(BRD1A-AIN2)") (class "Default")
      (node (ref "BRD1") (pin "20") (pinfunction "AIN2_20") (pintype "bidirectional"))
      (node (ref "BRD1") (pin "60") (pinfunction "AIN2_60") (pintype "bidirectional"))
    )
    (net (code "23") (name "Net-(BRD1A-GP0)") (class "Default")
      (node (ref "BRD1") (pin "16") (pinfunction "GP0_16") (pintype "bidirectional"))
      (node (ref "BRD1") (pin "56") (pinfunction "GP0_56") (pintype "bidirectional"))
    )
    (net (code "24") (name "Net-(BRD1A-GP1)") (class "Default")
      (node (ref "BRD1") (pin "17") (pinfunction "GP1_17") (pintype "bidirectional"))
      (node (ref "BRD1") (pin "57") (pinfunction "GP1_57") (pintype "bidirectional"))
    )
    (net (code "25") (name "Net-(BRD1A-GP2)") (class "Default")
      (node (ref "BRD1") (pin "24") (pinfunction "GP2_24") (pintype "bidirectional"))
      (node (ref "BRD1") (pin "64") (pinfunction "GP2_64") (pintype "bidirectional"))
    )
    (net (code "26") (name "Net-(BRD1A-GP3)") (class "Default")
      (node (ref "BRD1") (pin "25") (pinfunction "GP3_25") (pintype "bidirectional"))
      (node (ref "BRD1") (pin "65") (pinfunction "GP3_65") (pintype "bidirectional"))
    )
    (net (code "27") (name "Net-(BRD1A-GP5)") (class "Default")
      (node (ref "BRD1") (pin "34") (pinfunction "GP5_34") (pintype "bidirectional"))
      (node (ref "BRD1") (pin "74") (pinfunction "GP5_74") (pintype "bidirectional"))
    )
    (net (code "28") (name "Net-(BRD1A-GP6)") (class "Default")
      (node (ref "BRD1") (pin "35") (pinfunction "GP6_35") (pintype "bidirectional"))
      (node (ref "BRD1") (pin "75") (pinfunction "GP6_75") (pintype "bidirectional"))
    )
    (net (code "29") (name "Net-(BRD1A-GP7)") (class "Default")
      (node (ref "BRD1") (pin "36") (pinfunction "GP7_36") (pintype "bidirectional"))
      (node (ref "BRD1") (pin "76") (pinfunction "GP7_76") (pintype "bidirectional"))
    )
    (net (code "30") (name "Net-(BRD1A-MISO1)") (class "Default")
      (node (ref "BRD1") (pin "14") (pinfunction "MISO1_14") (pintype "bidirectional"))
      (node (ref "BRD1") (pin "54") (pinfunction "MISO1_54") (pintype "bidirectional"))
    )
    (net (code "31") (name "Net-(BRD1A-MISO2)") (class "Default")
      (node (ref "BRD1") (pin "27") (pinfunction "MISO2_27") (pintype "bidirectional"))
      (node (ref "BRD1") (pin "67") (pinfunction "MISO2_67") (pintype "bidirectional"))
    )
    (net (code "32") (name "Net-(BRD1A-MOSI1)") (class "Default")
      (node (ref "BRD1") (pin "13") (pinfunction "MOSI1_13") (pintype "bidirectional"))
      (node (ref "BRD1") (pin "53") (pinfunction "MOSI1_53") (pintype "bidirectional"))
    )
    (net (code "33") (name "Net-(BRD1A-MOSI2)") (class "Default")
      (node (ref "BRD1") (pin "28") (pinfunction "MOSI2_28") (pintype "bidirectional"))
      (node (ref "BRD1") (pin "68") (pinfunction "MOSI2_68") (pintype "bidirectional"))
    )
    (net (code "34") (name "Net-(BRD1A-PWM0)") (class "Default")
      (node (ref "BRD1") (pin "21") (pinfunction "PWM0_21") (pintype "bidirectional"))
      (node (ref "BRD1") (pin "61") (pinfunction "PWM0_61") (pintype "bidirectional"))
    )
    (net (code "35") (name "Net-(BRD1A-PWM1)") (class "Default")
      (node (ref "BRD1") (pin "22") (pinfunction "PWM1_22") (pintype "bidirectional"))
      (node (ref "BRD1") (pin "62") (pinfunction "PWM1_62") (pintype "bidirectional"))
    )
    (net (code "36") (name "Net-(BRD1A-PWM2)") (class "Default")
      (node (ref "BRD1") (pin "23") (pinfunction "PWM2_23") (pintype "bidirectional"))
      (node (ref "BRD1") (pin "63") (pinfunction "PWM2_63") (pintype "bidirectional"))
    )
    (net (code "37") (name "Net-(BRD1A-SCK1)") (class "Default")
      (node (ref "BRD1") (pin "15") (pinfunction "SCK1_15") (pintype "bidirectional"))
      (node (ref "BRD1") (pin "55") (pinfunction "SCK1_55") (pintype "bidirectional"))
    )
    (net (code "38") (name "Net-(BRD1A-SCK2)") (class "Default")
      (node (ref "BRD1") (pin "26") (pinfunction "SCK2_26") (pintype "bidirectional"))
      (node (ref "BRD1") (pin "66") (pinfunction "SCK2_66") (pintype "bidirectional"))
    )
    (net (code "39") (name "Net-(BRD1A-SCL1)") (class "Default")
      (node (ref "BRD1") (pin "12") (pinfunction "SCL1_12") (pintype "bidirectional"))
      (node (ref "BRD1") (pin "52") (pinfunction "SCL1_52") (pintype "bidirectional"))
    )
    (net (code "40") (name "Net-(BRD1A-SCL2)") (class "Default")
      (node (ref "BRD1") (pin "29") (pinfunction "SCL2_29") (pintype "bidirectional"))
      (node (ref "BRD1") (pin "69") (pinfunction "SCL2_69") (pintype "bidirectional"))
    )
    (net (code "41") (name "Net-(BRD1A-SDA1)") (class "Default")
      (node (ref "BRD1") (pin "11") (pinfunction "SDA1_11") (pintype "bidirectional"))
      (node (ref "BRD1") (pin "51") (pinfunction "SDA1_51") (pintype "bidirectional"))
    )
    (net (code "42") (name "Net-(BRD1A-SDA2)") (class "Default")
      (node (ref "BRD1") (pin "30") (pinfunction "SDA2_30") (pintype "bidirectional"))
      (node (ref "BRD1") (pin "70") (pinfunction "SDA2_70") (pintype "bidirectional"))
    )
    (net (code "43") (name "Net-(BRD1A-TGT_CTS)") (class "Default")
      (node (ref "BRD1") (pin "39") (pinfunction "TGT_CTS_39") (pintype "bidirectional"))
      (node (ref "BRD1") (pin "79") (pinfunction "TGT_CTS_79") (pintype "bidirectional"))
    )
    (net (code "44") (name "Net-(BRD1A-TGT_NRESET)") (class "Default")
      (node (ref "BRD1") (pin "46") (pinfunction "TGT_NRESET_46") (pintype "bidirectional"))
      (node (ref "BRD1") (pin "6") (pinfunction "TGT_NRESET_6") (pintype "bidirectional"))
    )
    (net (code "45") (name "Net-(BRD1A-TGT_RTS)") (class "Default")
      (node (ref "BRD1") (pin "38") (pinfunction "TGT_RTS_38") (pintype "bidirectional"))
      (node (ref "BRD1") (pin "78") (pinfunction "TGT_RTS_78") (pintype "bidirectional"))
    )
    (net (code "46") (name "Net-(BRD1A-TGT_RX)") (class "Default")
      (node (ref "BRD1") (pin "48") (pinfunction "TGT_RX_48") (pintype "bidirectional"))
      (node (ref "BRD1") (pin "8") (pinfunction "TGT_RX_8") (pintype "bidirectional"))
    )
    (net (code "47") (name "Net-(BRD1A-TGT_SWCLK)") (class "Default")
      (node (ref "BRD1") (pin "45") (pinfunction "TGT_SWCLK_45") (pintype "bidirectional"))
      (node (ref "BRD1") (pin "5") (pinfunction "TGT_SWCLK_5") (pintype "bidirectional"))
    )
    (net (code "48") (name "Net-(BRD1A-TGT_SWDIO)") (class "Default")
      (node (ref "BRD1") (pin "4") (pinfunction "TGT_SWDIO_4") (pintype "bidirectional"))
      (node (ref "BRD1") (pin "44") (pinfunction "TGT_SWDIO_44") (pintype "bidirectional"))
    )
    (net (code "49") (name "Net-(BRD1A-TGT_TX)") (class "Default")
      (node (ref "BRD1") (pin "47") (pinfunction "TGT_TX_47") (pintype "bidirectional"))
      (node (ref "BRD1") (pin "7") (pinfunction "TGT_TX_7") (pintype "bidirectional"))
    )
    (net (code "50") (name "Net-(C1-P$2)") (class "Default")
      (node (ref "C1") (pin "2") (pinfunction "P$2_2") (pintype "passive"))
      (node (ref "CON1") (pin "1") (pinfunction "1_1") (pintype "passive"))
      (node (ref "R1") (pin "1") (pinfunction "P$1_1") (pintype "passive"))
    )
    (net (code "51") (name "Net-(C2-P$2)") (class "Default")
      (node (ref "C2") (pin "2") (pinfunction "P$2_2") (pintype "passive"))
      (node (ref "MOD1") (pin "60") (pinfunction "ANT_MAIN_60") (pintype "bidirectional"))
      (node (ref "R1") (pin "2") (pinfunction "P$2_2") (pintype "passive"))
    )
    (net (code "52") (name "Net-(C11-P$1)") (class "Default")
      (node (ref "C11") (pin "1") (pinfunction "P$1_1") (pintype "passive"))
      (node (ref "C13") (pin "+") (pinfunction "+_+") (pintype "passive"))
      (node (ref "CON3") (pin "1-1") (pinfunction "PWR_1-1") (pintype "bidirectional"))
      (node (ref "CON3") (pin "1-2") (pinfunction "PWR_1-2") (pintype "bidirectional"))
      (node (ref "IC1") (pin "1") (pinfunction "EN_1") (pintype "bidirectional"))
      (node (ref "IC1") (pin "2") (pinfunction "VIN_2") (pintype "bidirectional"))
    )
    (net (code "53") (name "Net-(C12-P$1)") (class "Default")
      (node (ref "C12") (pin "1") (pinfunction "P$1_1") (pintype "passive"))
      (node (ref "C14") (pin "+") (pinfunction "+_+") (pintype "passive"))
      (node (ref "IC1") (pin "4") (pinfunction "OUT_4") (pintype "bidirectional"))
      (node (ref "R2") (pin "1") (pinfunction "P$1_1") (pintype "passive"))
      (node (ref "R3") (pin "1") (pinfunction "P$1_1") (pintype "passive"))
      (node (ref "R4") (pin "2") (pinfunction "P$2_2") (pintype "passive"))
      (node (ref "R6") (pin "2") (pinfunction "P$2_2") (pintype "passive"))
    )
    (net (code "54") (name "Net-(C15-P$2)") (class "Default")
      (node (ref "C15") (pin "2") (pinfunction "P$2_2") (pintype "passive"))
      (node (ref "CON4") (pin "1") (pinfunction "1_1") (pintype "passive"))
      (node (ref "R14") (pin "1") (pinfunction "P$1_1") (pintype "passive"))
    )
    (net (code "55") (name "Net-(C16-P$2)") (class "Default")
      (node (ref "C16") (pin "2") (pinfunction "P$2_2") (pintype "passive"))
      (node (ref "MOD1") (pin "49") (pinfunction "ANT_GNSS_49") (pintype "input"))
      (node (ref "R14") (pin "2") (pinfunction "P$2_2") (pintype "passive"))
    )
    (net (code "56") (name "Net-(C18-P$1)") (class "Default")
      (node (ref "C18") (pin "1") (pinfunction "P$1_1") (pintype "passive"))
      (node (ref "J1") (pin "C3") (pinfunction "CLK_C3") (pintype "input"))
      (node (ref "R20") (pin "2") (pinfunction "P$2_2") (pintype "passive"))
      (node (ref "TP28") (pin "TP") (pinfunction "TP_TP") (pintype "input"))
      (node (ref "U4") (pin "6") (pinfunction "CLK_6") (pintype "bidirectional"))
    )
    (net (code "57") (name "Net-(C21-P$1)") (class "Default")
      (node (ref "C21") (pin "1") (pinfunction "P$1_1") (pintype "passive"))
      (node (ref "IC2") (pin "2") (pinfunction "I1_2") (pintype "input"))
      (node (ref "J1") (pin "C2") (pinfunction "RST_C2") (pintype "input"))
      (node (ref "R19") (pin "2") (pinfunction "P$2_2") (pintype "passive"))
    )
    (net (code "58") (name "Net-(C23-P$1)") (class "Default")
      (node (ref "C23") (pin "1") (pinfunction "P$1_1") (pintype "passive"))
      (node (ref "J1") (pin "C7") (pinfunction "I/O_C7") (pintype "bidirectional"))
      (node (ref "R21") (pin "2") (pinfunction "P$2_2") (pintype "passive"))
      (node (ref "R22") (pin "1") (pinfunction "P$1_1") (pintype "passive"))
      (node (ref "TP27") (pin "TP") (pinfunction "TP_TP") (pintype "input"))
      (node (ref "U4") (pin "2") (pinfunction "IO_2") (pintype "bidirectional"))
    )
    (net (code "59") (name "Net-(CON2-PadD+)") (class "Default")
      (node (ref "CON2") (pin "D+") (pinfunction "D+_D+") (pintype "bidirectional"))
      (node (ref "U2") (pin "1") (pinfunction "IO1_1") (pintype "bidirectional"))
    )
    (net (code "60") (name "Net-(CON2-PadD-)") (class "Default")
      (node (ref "CON2") (pin "D-") (pinfunction "D-_D-") (pintype "bidirectional"))
      (node (ref "U2") (pin "3") (pinfunction "IO2_3") (pintype "bidirectional"))
    )
    (net (code "61") (name "Net-(IC1-ADJ)") (class "Default")
      (node (ref "IC1") (pin "5") (pinfunction "ADJ_5") (pintype "bidirectional"))
      (node (ref "R4") (pin "1") (pinfunction "P$1_1") (pintype "passive"))
      (node (ref "R5") (pin "2") (pinfunction "P$2_2") (pintype "passive"))
    )
    (net (code "62") (name "Net-(IC2A-O)") (class "Default")
      (node (ref "IC2") (pin "4") (pinfunction "O_4") (pintype "output"))
      (node (ref "TP29") (pin "TP") (pinfunction "TP_TP") (pintype "input"))
      (node (ref "U4") (pin "7") (pinfunction "RST_7") (pintype "bidirectional"))
    )
    (net (code "63") (name "Net-(J1-VPP)") (class "Default")
      (node (ref "J1") (pin "C6") (pinfunction "VPP_C6") (pintype "power_in"))
      (node (ref "TP31") (pin "TP") (pinfunction "TP_TP") (pintype "input"))
    )
    (net (code "64") (name "Net-(MOD1-ADC0)") (class "Default")
      (node (ref "MOD1") (pin "24") (pinfunction "ADC0_24") (pintype "input"))
      (node (ref "TP3") (pin "TP") (pinfunction "TP_TP") (pintype "input"))
    )
    (net (code "65") (name "Net-(MOD1-ADC1)") (class "Default")
      (node (ref "MOD1") (pin "2") (pinfunction "ADC1_2") (pintype "input"))
      (node (ref "TP4") (pin "TP") (pinfunction "TP_TP") (pintype "input"))
    )
    (net (code "66") (name "Net-(MOD1-AP_READY)") (class "Default")
      (node (ref "MOD1") (pin "19") (pinfunction "AP_READY_19") (pintype "input"))
      (node (ref "TP2") (pin "TP") (pinfunction "TP_TP") (pintype "input"))
    )
    (net (code "67") (name "Net-(MOD1-DCD)") (class "Default")
      (node (ref "MOD1") (pin "38") (pinfunction "DCD_38") (pintype "output"))
      (node (ref "TP18") (pin "TP") (pinfunction "TP_TP") (pintype "input"))
    )
    (net (code "68") (name "Net-(MOD1-DTR)") (class "Default")
      (node (ref "MOD1") (pin "30") (pinfunction "DTR_30") (pintype "input"))
      (node (ref "TP15") (pin "TP") (pinfunction "TP_TP") (pintype "input"))
    )
    (net (code "69") (name "Net-(MOD1-GPIO{slash}SPI_CLK)") (class "Default")
      (node (ref "MOD1") (pin "26") (pinfunction "GPIO/SPI_CLK_26") (pintype "output"))
      (node (ref "TP12") (pin "TP") (pinfunction "TP_TP") (pintype "input"))
    )
    (net (code "70") (name "Net-(MOD1-I2C_SCL)") (class "Default")
      (node (ref "MOD1") (pin "40") (pinfunction "I2C_SCL_40") (pintype "input"))
      (node (ref "TP13") (pin "TP") (pinfunction "TP_TP") (pintype "input"))
    )
    (net (code "71") (name "Net-(MOD1-I2C_SDA)") (class "Default")
      (node (ref "MOD1") (pin "41") (pinfunction "I2C_SDA_41") (pintype "bidirectional"))
      (node (ref "TP14") (pin "TP") (pinfunction "TP_TP") (pintype "input"))
    )
    (net (code "72") (name "Net-(MOD1-I2S_BCLK)") (class "Default")
      (node (ref "MOD1") (pin "4") (pinfunction "I2S_BCLK_4") (pintype "output"))
      (node (ref "TP22") (pin "TP") (pinfunction "TP_TP") (pintype "input"))
    )
    (net (code "73") (name "Net-(MOD1-I2S_D0)") (class "Default")
      (node (ref "MOD1") (pin "6") (pinfunction "I2S_D0_6") (pintype "bidirectional"))
      (node (ref "TP20") (pin "TP") (pinfunction "TP_TP") (pintype "input"))
    )
    (net (code "74") (name "Net-(MOD1-I2S_D1)") (class "Default")
      (node (ref "MOD1") (pin "7") (pinfunction "I2S_D1_7") (pintype "bidirectional"))
      (node (ref "TP21") (pin "TP") (pinfunction "TP_TP") (pintype "input"))
    )
    (net (code "75") (name "Net-(MOD1-I2S_WCLK)") (class "Default")
      (node (ref "MOD1") (pin "5") (pinfunction "I2S_WCLK_5") (pintype "output"))
      (node (ref "TP24") (pin "TP") (pinfunction "TP_TP") (pintype "input"))
    )
    (net (code "76") (name "Net-(MOD1-PSM_IND)") (class "Default")
      (node (ref "MOD1") (pin "1") (pinfunction "PSM_IND_1") (pintype "output"))
      (node (ref "TP25") (pin "TP") (pinfunction "TP_TP") (pintype "input"))
    )
    (net (code "77") (name "Net-(MOD1-RI)") (class "Default")
      (node (ref "MOD1") (pin "39") (pinfunction "RI_39") (pintype "output"))
      (node (ref "TP17") (pin "TP") (pinfunction "TP_TP") (pintype "input"))
    )
    (net (code "78") (name "Net-(MOD1-STATUS)") (class "Default")
      (node (ref "MOD1") (pin "20") (pinfunction "STATUS_20") (pintype "output"))
      (node (ref "R15") (pin "1") (pinfunction "P$1_1") (pintype "passive"))
    )
    (net (code "79") (name "Net-(MOD1-UART3_RXD{slash}SPI_MISO)") (class "Default")
      (node (ref "MOD1") (pin "28") (pinfunction "UART3_RXD/SPI_MISO_28") (pintype "input"))
      (node (ref "TP10") (pin "TP") (pinfunction "TP_TP") (pintype "input"))
    )
    (net (code "80") (name "Net-(MOD1-UART3_TXD{slash}SPI_MOSI)") (class "Default")
      (node (ref "MOD1") (pin "27") (pinfunction "UART3_TXD/SPI_MOSI_27") (pintype "output"))
      (node (ref "TP11") (pin "TP") (pinfunction "TP_TP") (pintype "input"))
    )
    (net (code "81") (name "Net-(MOD1-USB_DM)") (class "Default")
      (node (ref "MOD1") (pin "10") (pinfunction "USB_DM_10") (pintype "bidirectional"))
      (node (ref "U2") (pin "4") (pinfunction "IO2_4") (pintype "bidirectional"))
    )
    (net (code "82") (name "Net-(MOD1-USB_DP)") (class "Default")
      (node (ref "MOD1") (pin "9") (pinfunction "USB_DP_9") (pintype "bidirectional"))
      (node (ref "U2") (pin "6") (pinfunction "IO1_6") (pintype "bidirectional"))
    )
    (net (code "83") (name "Net-(MOD1-W_DISABLE#)") (class "Default")
      (node (ref "MOD1") (pin "18") (pinfunction "W_DISABLE#_18") (pintype "input"))
      (node (ref "TP1") (pin "TP") (pinfunction "TP_TP") (pintype "input"))
    )
    (net (code "84") (name "Net-(R7-P$2)") (class "Default")
      (node (ref "R7") (pin "2") (pinfunction "P$2_2") (pintype "passive"))
      (node (ref "R8") (pin "2") (pinfunction "P$2_2") (pintype "passive"))
      (node (ref "T1") (pin "1") (pinfunction "B_1") (pintype "passive"))
    )
    (net (code "85") (name "Net-(R10-P$2)") (class "Default")
      (node (ref "R10") (pin "2") (pinfunction "P$2_2") (pintype "passive"))
      (node (ref "R9") (pin "2") (pinfunction "P$2_2") (pintype "passive"))
      (node (ref "T2") (pin "1") (pinfunction "B_1") (pintype "passive"))
    )
    (net (code "86") (name "Net-(R11-P$2)") (class "Default")
      (node (ref "R11") (pin "2") (pinfunction "P$2_2") (pintype "passive"))
      (node (ref "R12") (pin "2") (pinfunction "P$2_2") (pintype "passive"))
      (node (ref "T3") (pin "1") (pinfunction "B_1") (pintype "passive"))
    )
    (net (code "87") (name "Net-(R13-P$1)") (class "Default")
      (node (ref "R13") (pin "1") (pinfunction "P$1_1") (pintype "passive"))
      (node (ref "T3") (pin "3") (pinfunction "C_3") (pintype "passive"))
    )
    (net (code "88") (name "Net-(R13-P$2)") (class "Default")
      (node (ref "LED1") (pin "C") (pinfunction "C_C") (pintype "passive"))
      (node (ref "R13") (pin "2") (pinfunction "P$2_2") (pintype "passive"))
    )
    (net (code "89") (name "Net-(R15-P$2)") (class "Default")
      (node (ref "LED2") (pin "C") (pinfunction "C_C") (pintype "passive"))
      (node (ref "R15") (pin "2") (pinfunction "P$2_2") (pintype "passive"))
    )
    (net (code "90") (name "Net-(R24-P$1)") (class "Default")
      (node (ref "LED4") (pin "A") (pinfunction "A_A") (pintype "passive"))
      (node (ref "R24") (pin "1") (pinfunction "P$1_1") (pintype "passive"))
    )
    (net (code "91") (name "PWRKEY") (class "Default")
      (node (ref "C17") (pin "2") (pinfunction "P$2_2") (pintype "passive"))
      (node (ref "MOD1") (pin "15") (pinfunction "PWRKEY_15") (pintype "input"))
      (node (ref "T2") (pin "3") (pinfunction "C_3") (pintype "passive"))
    )
    (net (code "92") (name "PWRKEY_CTL") (class "Default")
      (node (ref "BRD1") (pin "37") (pinfunction "GP8_37") (pintype "bidirectional"))
      (node (ref "R9") (pin "1") (pinfunction "P$1_1") (pintype "passive"))
    )
    (net (code "93") (name "SIM_VDD") (class "Default")
      (node (ref "C24") (pin "1") (pinfunction "P$1_1") (pintype "passive"))
      (node (ref "IC2") (pin "5") (pinfunction "VCC_5") (pintype "power_in"))
      (node (ref "J1") (pin "C1") (pinfunction "VCC_C1") (pintype "power_in"))
      (node (ref "MOD1") (pin "43") (pinfunction "USIM_VDD_43") (pintype "power_in"))
      (node (ref "R22") (pin "2") (pinfunction "P$2_2") (pintype "passive"))
      (node (ref "U4") (pin "8") (pinfunction "VDD_8") (pintype "bidirectional"))
    )
    (net (code "94") (name "USIM_CLK") (class "Default")
      (node (ref "MOD1") (pin "46") (pinfunction "USIM_CLK_46") (pintype "output"))
      (node (ref "R20") (pin "1") (pinfunction "P$1_1") (pintype "passive"))
    )
    (net (code "95") (name "USIM_DATA") (class "Default")
      (node (ref "MOD1") (pin "45") (pinfunction "USIM_DATA_45") (pintype "bidirectional"))
      (node (ref "R21") (pin "1") (pinfunction "P$1_1") (pintype "passive"))
    )
    (net (code "96") (name "USIM_PRESENCE") (class "Default")
      (node (ref "IC2") (pin "1") (pinfunction "I0_1") (pintype "input"))
      (node (ref "J1") (pin "DSW2") (pinfunction "DSW2_DSW2") (pintype "output"))
      (node (ref "MOD1") (pin "42") (pinfunction "USIM_PRESENCE_42") (pintype "input"))
      (node (ref "R23") (pin "1") (pinfunction "P$1_1") (pintype "passive"))
    )
    (net (code "97") (name "USIM_RST") (class "Default")
      (node (ref "MOD1") (pin "44") (pinfunction "USIM_RST_44") (pintype "output"))
      (node (ref "R19") (pin "1") (pinfunction "P$1_1") (pintype "passive"))
    )
    (net (code "98") (name "VBUS") (class "Default")
      (node (ref "CON2") (pin "VBUS") (pinfunction "VBUS_VBUS") (pintype "bidirectional"))
      (node (ref "MOD1") (pin "8") (pinfunction "USB_VBUS_8") (pintype "power_in"))
      (node (ref "U2") (pin "5") (pinfunction "VBUS_5") (pintype "bidirectional"))
    )
    (net (code "99") (name "unconnected-(BRD1A-RX2-Pad31)") (class "Default")
      (node (ref "BRD1") (pin "31") (pinfunction "RX2_31") (pintype "bidirectional"))
    )
    (net (code "100") (name "unconnected-(BRD1A-TX2-Pad32)") (class "Default")
      (node (ref "BRD1") (pin "32") (pinfunction "TX2_32") (pintype "bidirectional"))
    )
    (net (code "101") (name "unconnected-(BRD1B-AIN0-Pad58)") (class "Default")
      (node (ref "BRD1") (pin "58") (pinfunction "AIN0_58") (pintype "bidirectional"))
    )
    (net (code "102") (name "unconnected-(BRD1B-AIN1-Pad59)") (class "Default")
      (node (ref "BRD1") (pin "59") (pinfunction "AIN1_59") (pintype "bidirectional"))
    )
    (net (code "103") (name "unconnected-(BRD1B-GP4-Pad73)") (class "Default")
      (node (ref "BRD1") (pin "73") (pinfunction "GP4_73") (pintype "bidirectional"))
    )
    (net (code "104") (name "unconnected-(BRD1B-GP8-Pad77)") (class "Default")
      (node (ref "BRD1") (pin "77") (pinfunction "GP8_77") (pintype "bidirectional"))
    )
    (net (code "105") (name "unconnected-(BRD1B-RX1-Pad50)") (class "Default")
      (node (ref "BRD1") (pin "50") (pinfunction "RX1_50") (pintype "bidirectional"))
    )
    (net (code "106") (name "unconnected-(BRD1B-TX1-Pad49)") (class "Default")
      (node (ref "BRD1") (pin "49") (pinfunction "TX1_49") (pintype "bidirectional"))
    )
    (net (code "107") (name "unconnected-(MOD1-GPIO-Pad64)") (class "Default")
      (node (ref "MOD1") (pin "64") (pinfunction "GPIO_64") (pintype "bidirectional"))
    )
    (net (code "108") (name "unconnected-(MOD1-I2S_MCLK-Pad63)") (class "Default")
      (node (ref "MOD1") (pin "63") (pinfunction "I2S_MCLK_63") (pintype "output"))
    )
    (net (code "109") (name "unconnected-(MOD1-RESERVED-Pad11)") (class "Default")
      (node (ref "MOD1") (pin "11") (pinfunction "RESERVED_11") (pintype "no_connect"))
    )
    (net (code "110") (name "unconnected-(MOD1-RESERVED-Pad12)") (class "Default")
      (node (ref "MOD1") (pin "12") (pinfunction "RESERVED_12") (pintype "no_connect"))
    )
    (net (code "111") (name "unconnected-(MOD1-RESERVED-Pad13)") (class "Default")
      (node (ref "MOD1") (pin "13") (pinfunction "RESERVED_13") (pintype "no_connect"))
    )
    (net (code "112") (name "unconnected-(MOD1-RESERVED-Pad14)") (class "Default")
      (node (ref "MOD1") (pin "14") (pinfunction "RESERVED_14") (pintype "no_connect"))
    )
    (net (code "113") (name "unconnected-(MOD1-RESERVED-Pad16)") (class "Default")
      (node (ref "MOD1") (pin "16") (pinfunction "RESERVED_16") (pintype "no_connect"))
    )
    (net (code "114") (name "unconnected-(MOD1-RESERVED-Pad25)") (class "Default")
      (node (ref "MOD1") (pin "25") (pinfunction "RESERVED_25") (pintype "no_connect"))
    )
    (net (code "115") (name "unconnected-(MOD1-RESERVED-Pad51)") (class "Default")
      (node (ref "MOD1") (pin "51") (pinfunction "RESERVED_51") (pintype "no_connect"))
    )
    (net (code "116") (name "unconnected-(MOD1-RESERVED-Pad56)") (class "Default")
      (node (ref "MOD1") (pin "56") (pinfunction "RESERVED_56") (pintype "no_connect"))
    )
    (net (code "117") (name "unconnected-(MOD1-RESERVED-Pad57)") (class "Default")
      (node (ref "MOD1") (pin "57") (pinfunction "RESERVED_57") (pintype "no_connect"))
    )
    (net (code "118") (name "unconnected-(MOD1-RESERVED-Pad65)") (class "Default")
      (node (ref "MOD1") (pin "65") (pinfunction "RESERVED_65") (pintype "no_connect"))
    )
    (net (code "119") (name "unconnected-(MOD1-RESERVED-Pad66)") (class "Default")
      (node (ref "MOD1") (pin "66") (pinfunction "RESERVED_66") (pintype "no_connect"))
    )
    (net (code "120") (name "unconnected-(MOD1-RESERVED-Pad76)") (class "Default")
      (node (ref "MOD1") (pin "76") (pinfunction "RESERVED_76") (pintype "no_connect"))
    )
    (net (code "121") (name "unconnected-(MOD1-RESERVED-Pad77)") (class "Default")
      (node (ref "MOD1") (pin "77") (pinfunction "RESERVED_77") (pintype "no_connect"))
    )
    (net (code "122") (name "unconnected-(MOD1-RESERVED-Pad78)") (class "Default")
      (node (ref "MOD1") (pin "78") (pinfunction "RESERVED_78") (pintype "no_connect"))
    )
    (net (code "123") (name "unconnected-(MOD1-RESERVED-Pad83)") (class "Default")
      (node (ref "MOD1") (pin "83") (pinfunction "RESERVED_83") (pintype "no_connect"))
    )
    (net (code "124") (name "unconnected-(MOD1-RESERVED-Pad84)") (class "Default")
      (node (ref "MOD1") (pin "84") (pinfunction "RESERVED_84") (pintype "no_connect"))
    )
    (net (code "125") (name "unconnected-(MOD1-RESERVED-Pad85)") (class "Default")
      (node (ref "MOD1") (pin "85") (pinfunction "RESERVED_85") (pintype "no_connect"))
    )
    (net (code "126") (name "unconnected-(MOD1-RESERVED-Pad86)") (class "Default")
      (node (ref "MOD1") (pin "86") (pinfunction "RESERVED_86") (pintype "no_connect"))
    )
    (net (code "127") (name "unconnected-(MOD1-RESERVED-Pad87)") (class "Default")
      (node (ref "MOD1") (pin "87") (pinfunction "RESERVED_87") (pintype "no_connect"))
    )
    (net (code "128") (name "unconnected-(MOD1-RESERVED-Pad88)") (class "Default")
      (node (ref "MOD1") (pin "88") (pinfunction "RESERVED_88") (pintype "no_connect"))
    )
    (net (code "129") (name "unconnected-(MOD1-RESERVED-Pad92)") (class "Default")
      (node (ref "MOD1") (pin "92") (pinfunction "RESERVED_92") (pintype "no_connect"))
    )
    (net (code "130") (name "unconnected-(MOD1-RESERVED-Pad93)") (class "Default")
      (node (ref "MOD1") (pin "93") (pinfunction "RESERVED_93") (pintype "no_connect"))
    )
    (net (code "131") (name "unconnected-(MOD1-RESERVED-Pad94)") (class "Default")
      (node (ref "MOD1") (pin "94") (pinfunction "RESERVED_94") (pintype "no_connect"))
    )
    (net (code "132") (name "unconnected-(MOD1-RESERVED-Pad95)") (class "Default")
      (node (ref "MOD1") (pin "95") (pinfunction "RESERVED_95") (pintype "no_connect"))
    )
    (net (code "133") (name "unconnected-(MOD1-RESERVED-Pad96)") (class "Default")
      (node (ref "MOD1") (pin "96") (pinfunction "RESERVED_96") (pintype "no_connect"))
    )
    (net (code "134") (name "unconnected-(MOD1-RESERVED-Pad97)") (class "Default")
      (node (ref "MOD1") (pin "97") (pinfunction "RESERVED_97") (pintype "no_connect"))
    )
    (net (code "135") (name "unconnected-(MOD1-RESERVED-Pad98)") (class "Default")
      (node (ref "MOD1") (pin "98") (pinfunction "RESERVED_98") (pintype "no_connect"))
    )
    (net (code "136") (name "unconnected-(MOD1-RESERVED-Pad99)") (class "Default")
      (node (ref "MOD1") (pin "99") (pinfunction "RESERVED_99") (pintype "no_connect"))
    )
    (net (code "137") (name "unconnected-(MOD1-USB_BOOT-Pad75)") (class "Default")
      (node (ref "MOD1") (pin "75") (pinfunction "USB_BOOT_75") (pintype "input"))
    )
    (net (code "138") (name "unconnected-(U1-A7-Pad8)") (class "Default")
      (node (ref "U1") (pin "8") (pinfunction "A7_8") (pintype "bidirectional"))
    )
    (net (code "139") (name "unconnected-(U1-A8-Pad9)") (class "Default")
      (node (ref "U1") (pin "9") (pinfunction "A8_9") (pintype "bidirectional"))
    )
    (net (code "140") (name "unconnected-(U1-B7-Pad13)") (class "Default")
      (node (ref "U1") (pin "13") (pinfunction "B7_13") (pintype "bidirectional"))
    )
    (net (code "141") (name "unconnected-(U1-B8-Pad12)") (class "Default")
      (node (ref "U1") (pin "12") (pinfunction "B8_12") (pintype "bidirectional"))
    )
  )
)
